# S9706_color.net
KiCad netlist of a schematic drawn in EAGLE
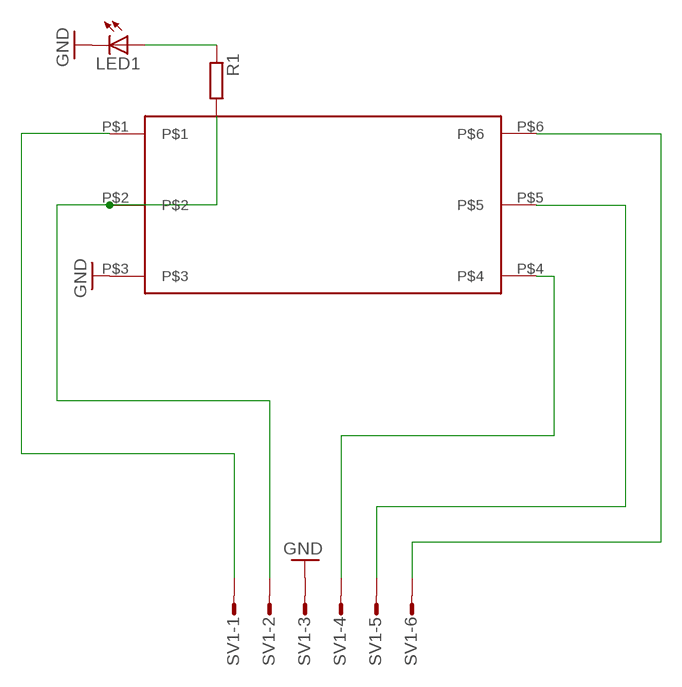
[diagram p0: schematic, sheet 1]

(export (version "E")
  (design (tool "Eeschema 10.0.6"))
  (components
    (comp (ref "LED1")
      (value "LED3MM")
      (footprint "eagle-import:LED3MM")
      (libsource (lib "eagle-import") (part "LED3MM"))
    )
    (comp (ref "R1")
      (value "R-EU_0204/2V")
      (footprint "eagle-import:0204V")
      (libsource (lib "eagle-import") (part "R-EU_0204/2V"))
    )
    (comp (ref "SV1")
      (value "S06P")
      (footprint "eagle-import:S06P")
      (libsource (lib "eagle-import") (part "S06P"))
    )
    (comp (ref "U$1")
      (value "S7906")
      (footprint "eagle-import:S9706")
      (libsource (lib "eagle-import") (part "S7906"))
    )
  )
  (nets
    (net (code "1") (name "GND") (class "Default")
      (node (ref "LED1") (pin "K") (pinfunction "C_K") (pintype "passive"))
      (node (ref "SV1") (pin "3") (pinfunction "S_3") (pintype "passive"))
      (node (ref "U$1") (pin "P$3") (pinfunction "P$3_P$3") (pintype "bidirectional"))
    )
    (net (code "2") (name "Net-(LED1-PadA)") (class "Default")
      (node (ref "LED1") (pin "A") (pinfunction "A_A") (pintype "passive"))
      (node (ref "R1") (pin "1") (pinfunction "1_1") (pintype "passive"))
    )
    (net (code "3") (name "Net-(SV1A-S)") (class "Default")
      (node (ref "SV1") (pin "1") (pinfunction "S_1") (pintype "passive"))
      (node (ref "U$1") (pin "P$1") (pinfunction "P$1_P$1") (pintype "bidirectional"))
    )
    (net (code "4") (name "Net-(SV1B-S)") (class "Default")
      (node (ref "R1") (pin "2") (pinfunction "2_2") (pintype "passive"))
      (node (ref "SV1") (pin "2") (pinfunction "S_2") (pintype "passive"))
      (node (ref "U$1") (pin "P$2") (pinfunction "P$2_P$2") (pintype "bidirectional"))
    )
    (net (code "5") (name "Net-(SV1D-S)") (class "Default")
      (node (ref "SV1") (pin "4") (pinfunction "S_4") (pintype "passive"))
      (node (ref "U$1") (pin "P$4") (pinfunction "P$4_P$4") (pintype "bidirectional"))
    )
    (net (code "6") (name "Net-(SV1E-S)") (class "Default")
      (node (ref "SV1") (pin "5") (pinfunction "S_5") (pintype "passive"))
      (node (ref "U$1") (pin "P$5") (pinfunction "P$5_P$5") (pintype "bidirectional"))
    )
    (net (code "7") (name "Net-(SV1F-S)") (class "Default")
      (node (ref "SV1") (pin "6") (pinfunction "S_6") (pintype "passive"))
      (node (ref "U$1") (pin "P$6") (pinfunction "P$6_P$6") (pintype "bidirectional"))
    )
  )
)
